# T962a_Panel.net
KiCad netlist of a schematic drawn in Altium Designer
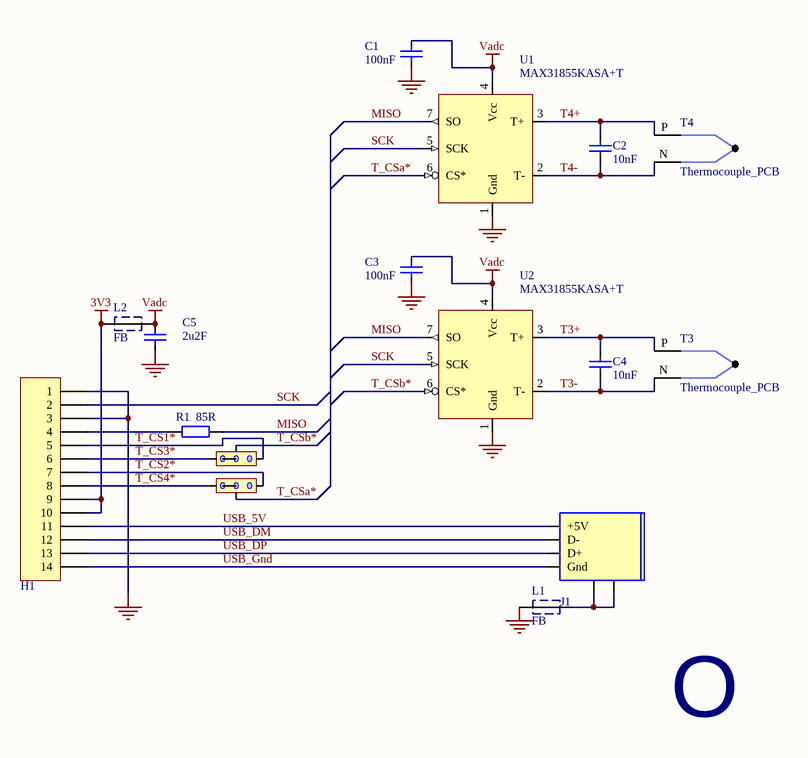
[diagram p0: T962a_Panel.SchDoc]

(export (version "E")
  (design (tool "Eeschema 10.0.6"))
  (components
    (comp (ref "C1")
      (value "100nF")
      (footprint "CCNP1608-0603")
      (description "Capacitor")
      (fields
        (field (name "MANUFACTURER") "Generic Components")
        (field (name "PUBLISHER") "Altium Hobart Technology Centre")
      )
      (libsource (lib "MyLibrary") (part "Cap"))
    )
    (comp (ref "C2")
      (value "10nF")
      (footprint "CCNP1608-0603")
      (description "Capacitor")
      (fields
        (field (name "MANUFACTURER") "Generic Components")
        (field (name "PUBLISHER") "Altium Hobart Technology Centre")
      )
      (libsource (lib "MyLibrary") (part "Cap"))
    )
    (comp (ref "C3")
      (value "100nF")
      (footprint "CCNP1608-0603")
      (description "Capacitor")
      (fields
        (field (name "MANUFACTURER") "Generic Components")
        (field (name "PUBLISHER") "Altium Hobart Technology Centre")
      )
      (libsource (lib "MyLibrary") (part "Cap"))
    )
    (comp (ref "C4")
      (value "10nF")
      (footprint "CCNP1608-0603")
      (description "Capacitor")
      (fields
        (field (name "MANUFACTURER") "Generic Components")
        (field (name "PUBLISHER") "Altium Hobart Technology Centre")
      )
      (libsource (lib "MyLibrary") (part "Cap"))
    )
    (comp (ref "C5")
      (value "2u2F")
      (footprint "CCNP2012-0805")
      (description "Capacitor")
      (fields
        (field (name "MANUFACTURER") "Generic Components")
        (field (name "PUBLISHER") "Altium Hobart Technology Centre")
      )
      (libsource (lib "MyLibrary") (part "Cap"))
    )
    (comp (ref "H1")
      (value "2x5 Header")
      (footprint "HDR2X7H")
      (description "Header 2x7")
      (libsource (lib "MyLibrary") (part "Header 2x7H"))
    )
    (comp (ref "J1")
      (value "USB Type B")
      (footprint "USB_BCon - straight pins")
      (description "USB B Connector")
      (libsource (lib "MyLibrary") (part "USB_TYPE_B"))
    )
    (comp (ref "L1")
      (value "FB")
      (footprint "CR2012-0805")
      (description "Ferrite Bead (0805) 0.045OHM, 2A")
      (libsource (lib "MyLibrary") (part "Ferrite Bead 0805"))
    )
    (comp (ref "L2")
      (value "FB")
      (footprint "CR2012-0805")
      (description "Ferrite Bead (0805) 0.045OHM, 2A")
      (libsource (lib "MyLibrary") (part "Ferrite Bead 0805"))
    )
    (comp (ref "Logo")
      (value "OSHW Logo")
      (footprint "OSHW")
      (libsource (lib "MyLibrary") (part "OSHW Logo"))
    )
    (comp (ref "R1")
      (value "85R")
      (footprint "CR2012-0805")
      (description "Resistor")
      (fields
        (field (name "MANUFACTURER") "Generic Components")
        (field (name "PUBLISHER") "Altium Hobart Technology Centre")
      )
      (libsource (lib "MyLibrary") (part "Res"))
    )
    (comp (ref "S1")
      (value "Link3Closed")
      (footprint "SolderBridge3(Closed)")
      (libsource (lib "") (part "Link3Closed_1"))
    )
    (comp (ref "S2")
      (value "Link3Closed")
      (footprint "SolderBridge3(Closed)")
      (libsource (lib "MyLibrary") (part "Link3Closed"))
    )
    (comp (ref "T3")
      (value "Thermocouple_PCB")
      (footprint "ThermoCoupleSocket - PCB mount")
      (libsource (lib "MySchLib") (part "Thermocouple_PCB"))
    )
    (comp (ref "T4")
      (value "Thermocouple_PCB")
      (footprint "ThermoCoupleSocket - PCB mount")
      (libsource (lib "MySchLib") (part "Thermocouple_PCB"))
    )
    (comp (ref "U1")
      (value "MAX31855KASA+T")
      (footprint "SO-8_L")
      (libsource (lib "MySchLib") (part "MAX31855KASA+T"))
    )
    (comp (ref "U2")
      (value "MAX31855KASA+T")
      (footprint "SO-8_L")
      (libsource (lib "MySchLib") (part "MAX31855KASA+T"))
    )
  )
  (nets
    (net (code "1") (name "/MISO") (class "Default")
      (node (ref "R1") (pin "2") (pinfunction "2_2") (pintype "passive"))
      (node (ref "U1") (pin "7") (pinfunction "SO_7") (pintype "output"))
      (node (ref "U2") (pin "7") (pinfunction "SO_7") (pintype "output"))
    )
    (net (code "2") (name "/SCK") (class "Default")
      (node (ref "H1") (pin "2") (pinfunction "2_2") (pintype "passive"))
      (node (ref "U1") (pin "5") (pinfunction "SCK_5") (pintype "input"))
      (node (ref "U2") (pin "5") (pinfunction "SCK_5") (pintype "input"))
    )
    (net (code "3") (name "/T3+") (class "Default")
      (node (ref "C4") (pin "1") (pinfunction "1_1") (pintype "passive"))
      (node (ref "T3") (pin "P") (pinfunction "P_P") (pintype "passive"))
      (node (ref "U2") (pin "3") (pinfunction "T+_3") (pintype "passive"))
    )
    (net (code "4") (name "/T3-") (class "Default")
      (node (ref "C4") (pin "2") (pinfunction "2_2") (pintype "passive"))
      (node (ref "T3") (pin "N") (pinfunction "N_N") (pintype "passive"))
      (node (ref "U2") (pin "2") (pinfunction "T-_2") (pintype "passive"))
    )
    (net (code "5") (name "/T4+") (class "Default")
      (node (ref "C2") (pin "1") (pinfunction "1_1") (pintype "passive"))
      (node (ref "T4") (pin "P") (pinfunction "P_P") (pintype "passive"))
      (node (ref "U1") (pin "3") (pinfunction "T+_3") (pintype "passive"))
    )
    (net (code "6") (name "/T4-") (class "Default")
      (node (ref "C2") (pin "2") (pinfunction "2_2") (pintype "passive"))
      (node (ref "T4") (pin "N") (pinfunction "N_N") (pintype "passive"))
      (node (ref "U1") (pin "2") (pinfunction "T-_2") (pintype "passive"))
    )
    (net (code "7") (name "/T_CS1*") (class "Default")
      (node (ref "H1") (pin "5") (pinfunction "5_5") (pintype "passive"))
      (node (ref "S1") (pin "3") (pintype "passive"))
    )
    (net (code "8") (name "/T_CS2*") (class "Default")
      (node (ref "H1") (pin "7") (pinfunction "7_7") (pintype "passive"))
      (node (ref "S2") (pin "3") (pintype "passive"))
    )
    (net (code "9") (name "/T_CS3*") (class "Default")
      (node (ref "H1") (pin "6") (pinfunction "6_6") (pintype "passive"))
      (node (ref "S1") (pin "1") (pintype "passive"))
    )
    (net (code "10") (name "/T_CS4*") (class "Default")
      (node (ref "H1") (pin "8") (pinfunction "8_8") (pintype "passive"))
      (node (ref "S2") (pin "1") (pintype "passive"))
    )
    (net (code "11") (name "/T_CSa*") (class "Default")
      (node (ref "S2") (pin "2") (pintype "passive"))
      (node (ref "U1") (pin "6") (pinfunction "CS*_6") (pintype "input"))
    )
    (net (code "12") (name "/T_CSb*") (class "Default")
      (node (ref "S1") (pin "2") (pintype "passive"))
      (node (ref "U2") (pin "6") (pinfunction "CS*_6") (pintype "input"))
    )
    (net (code "13") (name "/USB_5V") (class "Default")
      (node (ref "H1") (pin "11") (pinfunction "11_11") (pintype "passive"))
      (node (ref "J1") (pin "5V") (pinfunction "+5V_5V") (pintype "power_in"))
    )
    (net (code "14") (name "/USB_DM") (class "Default")
      (node (ref "H1") (pin "12") (pinfunction "12_12") (pintype "passive"))
      (node (ref "J1") (pin "D-") (pinfunction "D-_D-") (pintype "passive"))
    )
    (net (code "15") (name "/USB_DP") (class "Default")
      (node (ref "H1") (pin "13") (pinfunction "13_13") (pintype "passive"))
      (node (ref "J1") (pin "D+") (pinfunction "D+_D+") (pintype "passive"))
    )
    (net (code "16") (name "/USB_Gnd") (class "Default")
      (node (ref "H1") (pin "14") (pinfunction "14_14") (pintype "passive"))
      (node (ref "J1") (pin "Gnd") (pinfunction "Gnd_Gnd") (pintype "passive"))
    )
    (net (code "17") (name "3V3") (class "Default")
      (node (ref "H1") (pin "10") (pinfunction "10_10") (pintype "passive"))
      (node (ref "H1") (pin "9") (pinfunction "9_9") (pintype "passive"))
      (node (ref "L2") (pin "1") (pinfunction "1_1") (pintype "passive"))
    )
    (net (code "18") (name "GND") (class "Default")
      (node (ref "C1") (pin "1") (pinfunction "1_1") (pintype "passive"))
      (node (ref "C3") (pin "1") (pinfunction "1_1") (pintype "passive"))
      (node (ref "C5") (pin "1") (pinfunction "1_1") (pintype "passive"))
      (node (ref "H1") (pin "1") (pinfunction "1_1") (pintype "passive"))
      (node (ref "H1") (pin "3") (pinfunction "3_3") (pintype "passive"))
      (node (ref "L1") (pin "1") (pinfunction "1_1") (pintype "passive"))
      (node (ref "U1") (pin "1") (pinfunction "Gnd_1") (pintype "power_in"))
      (node (ref "U2") (pin "1") (pinfunction "Gnd_1") (pintype "power_in"))
    )
    (net (code "19") (name "Net-(H1-Pad4)") (class "Default")
      (node (ref "H1") (pin "4") (pinfunction "4_4") (pintype "passive"))
      (node (ref "R1") (pin "1") (pinfunction "1_1") (pintype "passive"))
    )
    (net (code "20") (name "Net-(J1-USBShd-PadShield1)") (class "Default")
      (node (ref "J1") (pin "Shield1") (pinfunction "USBShd_Shield1") (pintype "passive"))
      (node (ref "J1") (pin "Shield2") (pinfunction "USBShd_Shield2") (pintype "passive"))
      (node (ref "L1") (pin "2") (pinfunction "2_2") (pintype "passive"))
    )
    (net (code "21") (name "Vadc") (class "Default")
      (node (ref "C1") (pin "2") (pinfunction "2_2") (pintype "passive"))
      (node (ref "C3") (pin "2") (pinfunction "2_2") (pintype "passive"))
      (node (ref "C5") (pin "2") (pinfunction "2_2") (pintype "passive"))
      (node (ref "L2") (pin "2") (pinfunction "2_2") (pintype "passive"))
      (node (ref "U1") (pin "4") (pinfunction "Vcc_4") (pintype "power_in"))
      (node (ref "U2") (pin "4") (pinfunction "Vcc_4") (pintype "power_in"))
    )
    (net (code "22") (name "unconnected-(U1-NC-Pad8)") (class "Default")
      (node (ref "U1") (pin "8") (pinfunction "NC_8") (pintype "passive"))
    )
    (net (code "23") (name "unconnected-(U2-NC-Pad8)") (class "Default")
      (node (ref "U2") (pin "8") (pinfunction "NC_8") (pintype "passive"))
    )
  )
)
